# SY8105ADC.net
KiCad netlist of a schematic drawn in Altium Designer
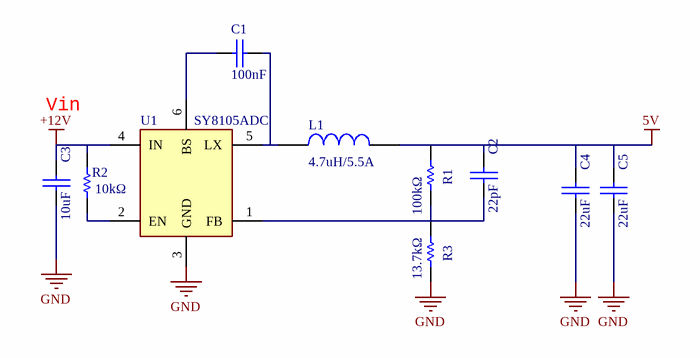
[diagram p0: SY8105ADC.SchDoc]

(export (version "E")
  (design (tool "Eeschema 10.0.6"))
  (components
    (comp (ref "C1")
      (value "100nF")
      (footprint "C_0402")
      (description "贴片电容")
      (libsource (lib "IntLib-Passive") (part "Cap_Chip"))
    )
    (comp (ref "C2")
      (value "22pF")
      (footprint "C_0402")
      (description "贴片电容")
      (libsource (lib "IntLib-Passive") (part "Cap_Chip"))
    )
    (comp (ref "C3")
      (value "10uF")
      (footprint "C_0805")
      (description "贴片电容")
      (libsource (lib "IntLib-Passive") (part "Cap_Chip"))
    )
    (comp (ref "C4")
      (value "22uF")
      (footprint "C_0805")
      (description "贴片电容")
      (libsource (lib "IntLib-Passive") (part "Cap_Chip"))
    )
    (comp (ref "C5")
      (value "22uF")
      (footprint "C_0805")
      (description "贴片电容")
      (libsource (lib "IntLib-Passive") (part "Cap_Chip"))
    )
    (comp (ref "L1")
      (value "4.7uH/5.5A")
      (footprint "Ind-SMD_7.3x6.6")
      (description "一体成型功率电感")
      (fields (field (name "MANUFACTURER_PART_NUMBER") "SLO0630H4R7MTT"))
      (libsource (lib "IntLib-Passive") (part "Ind_Molded"))
    )
    (comp (ref "R1")
      (value "100kΩ")
      (footprint "R_0402")
      (description "贴片电阻")
      (libsource (lib "IntLib-Passive") (part "Res_Chip"))
    )
    (comp (ref "R2")
      (value "10kΩ")
      (footprint "R_0402")
      (description "贴片电阻")
      (libsource (lib "IntLib-Passive") (part "Res_Chip"))
    )
    (comp (ref "R3")
      (value "13.7kΩ")
      (footprint "R_0402")
      (description "贴片电阻")
      (libsource (lib "IntLib-Passive") (part "Res_Chip"))
    )
    (comp (ref "U1")
      (value "SY8105ADC")
      (footprint "SOT23-6")
      (description "DC-DC芯片")
      (libsource (lib "IntLib-IC") (part "SY8105ADC"))
    )
  )
  (nets
    (net (code "1") (name "+12V") (class "Default")
      (node (ref "C3") (pin "1") (pinfunction "1_1") (pintype "passive"))
      (node (ref "R2") (pin "2") (pinfunction "2_2") (pintype "passive"))
      (node (ref "U1") (pin "4") (pinfunction "IN_4") (pintype "passive"))
    )
    (net (code "2") (name "5V") (class "Default")
      (node (ref "C2") (pin "1") (pinfunction "1_1") (pintype "passive"))
      (node (ref "C4") (pin "1") (pinfunction "1_1") (pintype "passive"))
      (node (ref "C5") (pin "1") (pinfunction "1_1") (pintype "passive"))
      (node (ref "L1") (pin "2") (pinfunction "2_2") (pintype "passive"))
      (node (ref "R1") (pin "1") (pinfunction "1_1") (pintype "passive"))
    )
    (net (code "3") (name "GND") (class "Default")
      (node (ref "C3") (pin "2") (pinfunction "2_2") (pintype "passive"))
      (node (ref "C4") (pin "2") (pinfunction "2_2") (pintype "passive"))
      (node (ref "C5") (pin "2") (pinfunction "2_2") (pintype "passive"))
      (node (ref "R3") (pin "2") (pinfunction "2_2") (pintype "passive"))
      (node (ref "U1") (pin "3") (pinfunction "GND_3") (pintype "passive"))
    )
    (net (code "4") (name "Net-(U1-BS)") (class "Default")
      (node (ref "C1") (pin "2") (pinfunction "2_2") (pintype "passive"))
      (node (ref "U1") (pin "6") (pinfunction "BS_6") (pintype "passive"))
    )
    (net (code "5") (name "Net-(U1-EN)") (class "Default")
      (node (ref "R2") (pin "1") (pinfunction "1_1") (pintype "passive"))
      (node (ref "U1") (pin "2") (pinfunction "EN_2") (pintype "passive"))
    )
    (net (code "6") (name "Net-(U1-FB)") (class "Default")
      (node (ref "C2") (pin "2") (pinfunction "2_2") (pintype "passive"))
      (node (ref "R1") (pin "2") (pinfunction "2_2") (pintype "passive"))
      (node (ref "R3") (pin "1") (pinfunction "1_1") (pintype "passive"))
      (node (ref "U1") (pin "1") (pinfunction "FB_1") (pintype "passive"))
    )
    (net (code "7") (name "Net-(U1-LX)") (class "Default")
      (node (ref "C1") (pin "1") (pinfunction "1_1") (pintype "passive"))
      (node (ref "L1") (pin "1") (pinfunction "1_1") (pintype "passive"))
      (node (ref "U1") (pin "5") (pinfunction "LX_5") (pintype "passive"))
    )
  )
)
